# EtherCAT_Sheet.net
KiCad netlist of a schematic drawn in Altium Designer
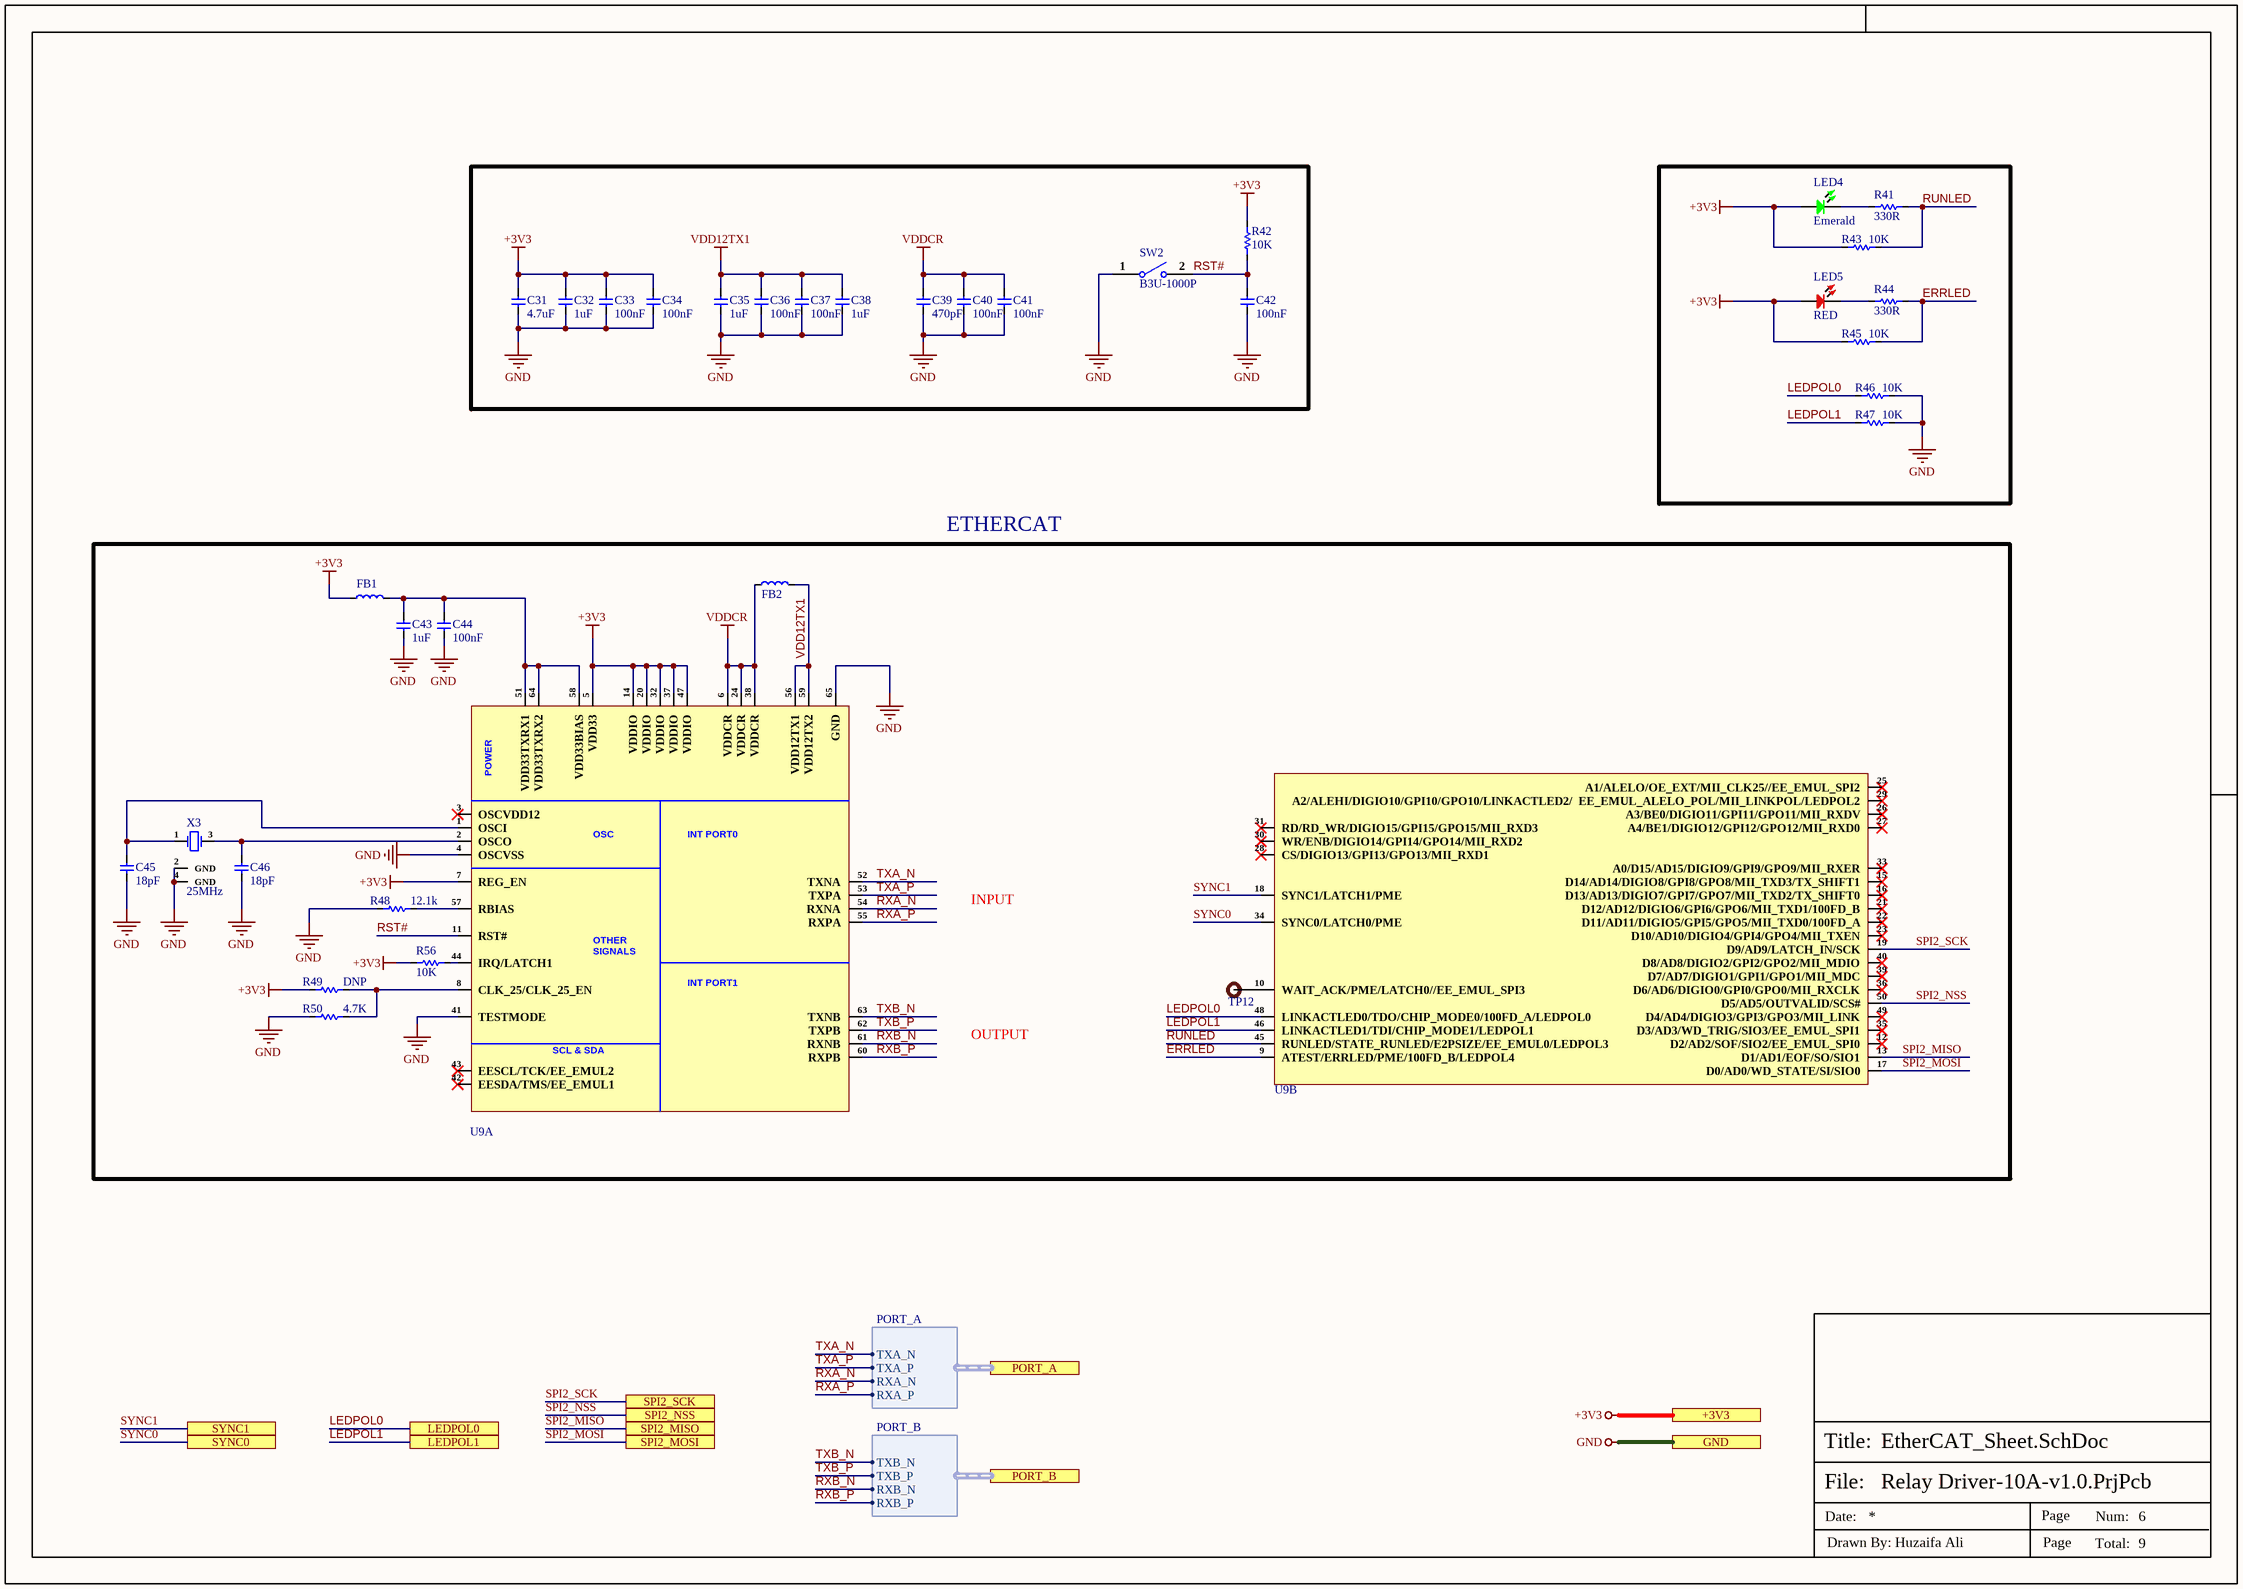
[diagram p0: EtherCAT_Sheet.SchDoc]

(export (version "E")
  (design (tool "Eeschema 10.0.6"))
  (components
    (comp (ref "C31")
      (value "4.7uF")
      (footprint "Cap-0402")
      (description "CAP CER 4.7UF 10V X5R 0402")
      (fields
        (field (name "MANUFACTURER") "Yageo")
        (field (name "MANUFACTURER PART NUMBER") "CC0402KRX5R6BB475")
      )
      (libsource (lib "eSpark Libraries") (part "CC0402KRX5R6BB475"))
    )
    (comp (ref "C32")
      (value "1uF")
      (footprint "Cap-0402")
      (description "CAP CER 1UF 10V X5R 0402")
      (fields
        (field (name "MANUFACTURER") "Yageo")
        (field (name "MANUFACTURER PART NUMBER") "CC0402KRX5R6BB105")
      )
      (libsource (lib "eSpark Libraries") (part "CC0402KRX5R6BB105"))
    )
    (comp (ref "C33")
      (value "100nF")
      (footprint "cap-0402")
      (description "CAP CER 0.1UF 50V X7R 0402")
      (fields
        (field (name "MANUFACTURER") "TDK")
        (field (name "MANUFACTURER PART NUMBER") "C1005X7R1H104KT000F")
      )
      (libsource (lib "eSpark Libraries") (part "C1005X7R1H104KT000F"))
    )
    (comp (ref "C34")
      (value "100nF")
      (footprint "cap-0402")
      (description "CAP CER 0.1UF 50V X7R 0402")
      (fields
        (field (name "MANUFACTURER") "TDK")
        (field (name "MANUFACTURER PART NUMBER") "C1005X7R1H104KT000F")
      )
      (libsource (lib "eSpark Libraries") (part "C1005X7R1H104KT000F"))
    )
    (comp (ref "C35")
      (value "1uF")
      (footprint "Cap-0402")
      (description "CAP CER 1UF 10V X5R 0402")
      (fields
        (field (name "MANUFACTURER") "Yageo")
        (field (name "MANUFACTURER PART NUMBER") "CC0402KRX5R6BB105")
      )
      (libsource (lib "eSpark Libraries") (part "CC0402KRX5R6BB105"))
    )
    (comp (ref "C36")
      (value "100nF")
      (footprint "cap-0402")
      (description "CAP CER 0.1UF 50V X7R 0402")
      (fields
        (field (name "MANUFACTURER") "TDK")
        (field (name "MANUFACTURER PART NUMBER") "C1005X7R1H104KT000F")
      )
      (libsource (lib "eSpark Libraries") (part "C1005X7R1H104KT000F"))
    )
    (comp (ref "C37")
      (value "100nF")
      (footprint "cap-0402")
      (description "CAP CER 0.1UF 50V X7R 0402")
      (fields
        (field (name "MANUFACTURER") "TDK")
        (field (name "MANUFACTURER PART NUMBER") "C1005X7R1H104KT000F")
      )
      (libsource (lib "eSpark Libraries") (part "C1005X7R1H104KT000F"))
    )
    (comp (ref "C38")
      (value "1uF")
      (footprint "Cap-0402")
      (description "CAP CER 1UF 10V X5R 0402")
      (fields
        (field (name "MANUFACTURER") "Yageo")
        (field (name "MANUFACTURER PART NUMBER") "CC0402KRX5R6BB105")
      )
      (libsource (lib "eSpark Libraries") (part "CC0402KRX5R6BB105"))
    )
    (comp (ref "C39")
      (value "470pF")
      (footprint "Cap-0603")
      (description "CAP CER 470PF 50V X7R 0603")
      (fields
        (field (name "MANUFACTURER") "Walsin Technologies")
        (field (name "MANUFACTURER PART NUMBER") "0603B471K500CT")
      )
      (libsource (lib "eSpark Libraries") (part "0603B471K500CT"))
    )
    (comp (ref "C40")
      (value "100nF")
      (footprint "cap-0402")
      (description "CAP CER 0.1UF 50V X7R 0402")
      (fields
        (field (name "MANUFACTURER") "TDK")
        (field (name "MANUFACTURER PART NUMBER") "C1005X7R1H104KT000F")
      )
      (libsource (lib "eSpark Libraries") (part "C1005X7R1H104KT000F"))
    )
    (comp (ref "C41")
      (value "100nF")
      (footprint "cap-0402")
      (description "CAP CER 0.1UF 50V X7R 0402")
      (fields
        (field (name "MANUFACTURER") "TDK")
        (field (name "MANUFACTURER PART NUMBER") "C1005X7R1H104KT000F")
      )
      (libsource (lib "eSpark Libraries") (part "C1005X7R1H104KT000F"))
    )
    (comp (ref "C42")
      (value "100nF")
      (footprint "cap-0402")
      (description "CAP CER 0.1UF 50V X7R 0402")
      (fields
        (field (name "MANUFACTURER") "TDK")
        (field (name "MANUFACTURER PART NUMBER") "C1005X7R1H104KT000F")
      )
      (libsource (lib "eSpark Libraries") (part "C1005X7R1H104KT000F"))
    )
    (comp (ref "C43")
      (value "1uF")
      (footprint "Cap-0402")
      (description "CAP CER 1UF 10V X5R 0402")
      (fields
        (field (name "MANUFACTURER") "Yageo")
        (field (name "MANUFACTURER PART NUMBER") "CC0402KRX5R6BB105")
      )
      (libsource (lib "eSpark Libraries") (part "CC0402KRX5R6BB105"))
    )
    (comp (ref "C44")
      (value "100nF")
      (footprint "cap-0402")
      (description "CAP CER 0.1UF 50V X7R 0402")
      (fields
        (field (name "MANUFACTURER") "TDK")
        (field (name "MANUFACTURER PART NUMBER") "C1005X7R1H104KT000F")
      )
      (libsource (lib "eSpark Libraries") (part "C1005X7R1H104KT000F"))
    )
    (comp (ref "C45")
      (value "18pF")
      (footprint "Cap-0402")
      (description "CAP CER 18PF 50V C0G/NP0 0402")
      (fields
        (field (name "MANUFACTURER") "Murata")
        (field (name "MANUFACTURER PART NUMBER") "GCM1555C1H180GA16D")
      )
      (libsource (lib "eSpark Libraries") (part "GCM1555C1H180GA16D"))
    )
    (comp (ref "C46")
      (value "18pF")
      (footprint "Cap-0402")
      (description "CAP CER 18PF 50V C0G/NP0 0402")
      (fields
        (field (name "MANUFACTURER") "Murata")
        (field (name "MANUFACTURER PART NUMBER") "GCM1555C1H180GA16D")
      )
      (libsource (lib "eSpark Libraries") (part "GCM1555C1H180GA16D"))
    )
    (comp (ref "FB1")
      (value "BLM15PG100SN1D")
      (footprint "IND-0402")
      (description "FERRITE BEAD 10 OHM 0402 1LN")
      (fields (field (name "MANUFACTURER") "Murata") (field (name "TOLERANCE") "25%"))
      (libsource (lib "eSpark Libraries") (part "BLM15PG100SN1D"))
    )
    (comp (ref "FB2")
      (value "BLM15PG100SN1D")
      (footprint "IND-0402")
      (description "FERRITE BEAD 10 OHM 0402 1LN")
      (fields (field (name "MANUFACTURER") "Murata") (field (name "TOLERANCE") "25%"))
      (libsource (lib "eSpark Libraries") (part "BLM15PG100SN1D"))
    )
    (comp (ref "LED4")
      (value "Emerald")
      (footprint "LED-0603")
      (description "Emerald 0603 Light Emitting Diodes (LED) ROHS")
      (fields
        (field (name "MANUFACTURER") "Foshan NationStar Optoelectronics")
        (field (name "MANUFACTURER PART NUMBER") "NCD0603G2")
      )
      (libsource (lib "eSpark Libraries") (part "NCD0603G2"))
    )
    (comp (ref "LED5")
      (value "RED")
      (footprint "LED-0603")
      (description "RED LED 0603 Light Emitting Diodes")
      (fields
        (field (name "MANUFACTURER") "Foshan NationStar Optoelectronics")
        (field (name "MANUFACTURER PART NUMBER") "NCD0603R3")
      )
      (libsource (lib "eSpark Libraries") (part "NCD0603R3"))
    )
    (comp (ref "R41")
      (value "330R")
      (footprint "Res-0603")
      (description "RES  SMD 330R 100 mW 0603")
      (fields
        (field (name "MANUFACTURER") "Yageo")
        (field (name "MANUFACTURER PART NUMBER") "RC0603JR-07330RL")
      )
      (libsource (lib "eSpark Libraries") (part "RC0603JR-07330RL"))
    )
    (comp (ref "R42")
      (value "10K")
      (footprint "Res-0402")
      (description "RES 10K OHM 1% 1/16W 0402")
      (fields
        (field (name "MANUFACTURER") "Yageo")
        (field (name "MANUFACTURER PART NUMBER") "RC0402FR-0710KL")
      )
      (libsource (lib "eSpark Libraries") (part "RC0402FR-0710KL"))
    )
    (comp (ref "R43")
      (value "10K")
      (footprint "Res-0402")
      (description "RES 10K OHM 1% 1/16W 0402")
      (fields
        (field (name "MANUFACTURER") "Yageo")
        (field (name "MANUFACTURER PART NUMBER") "RC0402FR-0710KL")
      )
      (libsource (lib "eSpark Libraries") (part "RC0402FR-0710KL"))
    )
    (comp (ref "R44")
      (value "330R")
      (footprint "Res-0603")
      (description "RES  SMD 330R 100 mW 0603")
      (fields
        (field (name "MANUFACTURER") "Yageo")
        (field (name "MANUFACTURER PART NUMBER") "RC0603JR-07330RL")
      )
      (libsource (lib "eSpark Libraries") (part "RC0603JR-07330RL"))
    )
    (comp (ref "R45")
      (value "10K")
      (footprint "Res-0402")
      (description "RES 10K OHM 1% 1/16W 0402")
      (fields
        (field (name "MANUFACTURER") "Yageo")
        (field (name "MANUFACTURER PART NUMBER") "RC0402FR-0710KL")
      )
      (libsource (lib "eSpark Libraries") (part "RC0402FR-0710KL"))
    )
    (comp (ref "R46")
      (value "10K")
      (footprint "Res-0402")
      (description "RES 10K OHM 1% 1/16W 0402")
      (fields
        (field (name "MANUFACTURER") "Yageo")
        (field (name "MANUFACTURER PART NUMBER") "RC0402FR-0710KL")
      )
      (libsource (lib "eSpark Libraries") (part "RC0402FR-0710KL"))
    )
    (comp (ref "R47")
      (value "10K")
      (footprint "Res-0402")
      (description "RES 10K OHM 1% 1/16W 0402")
      (fields
        (field (name "MANUFACTURER") "Yageo")
        (field (name "MANUFACTURER PART NUMBER") "RC0402FR-0710KL")
      )
      (libsource (lib "eSpark Libraries") (part "RC0402FR-0710KL"))
    )
    (comp (ref "R48")
      (value "12.1k")
      (footprint "Res-0402")
      (description "RES SMD 12.1KOHM 0.1% 1/16W 0402")
      (fields
        (field (name "MANUFACTURER") "Yageo")
        (field (name "MANUFACTURER PART NUMBER") "RT0402BRD0712K1L")
      )
      (libsource (lib "eSpark Libraries") (part "RT0402BRD0712K1L"))
    )
    (comp (ref "R49")
      (value "DNP")
      (footprint "Res-0402")
      (description "RES 4.7K OHM 1% 1/16W 0402")
      (fields
        (field (name "MANUFACTURER") "Yageo")
        (field (name "MANUFACTURER PART NUMBER") "RC0402FR-074K7L")
      )
      (libsource (lib "eSpark Libraries") (part "RC0402FR-074K7L"))
    )
    (comp (ref "R50")
      (value "4.7K")
      (footprint "Res-0402")
      (description "RES 4.7K OHM 1% 1/16W 0402")
      (fields
        (field (name "MANUFACTURER") "Yageo")
        (field (name "MANUFACTURER PART NUMBER") "RC0402FR-074K7L")
      )
      (libsource (lib "eSpark Libraries") (part "RC0402FR-074K7L"))
    )
    (comp (ref "R56")
      (value "10K")
      (footprint "Res-0402")
      (description "RES 10K OHM 1% 1/16W 0402")
      (fields
        (field (name "MANUFACTURER") "Yageo")
        (field (name "MANUFACTURER PART NUMBER") "RC0402FR-0710KL")
      )
      (libsource (lib "eSpark Libraries") (part "RC0402FR-0710KL"))
    )
    (comp (ref "SW2")
      (value "B3U-1000P")
      (footprint "B3U-1000P")
      (description "SWITCH TACTILE SPST-NO 0.05A 12V")
      (fields (field (name "MANUFACTURER") "Omron") (field (name "LCSC PART NUMBER") "C231329"))
      (libsource (lib "eSpark Libraries") (part "B3U-1000P"))
    )
    (comp (ref "TP12")
      (value "TEST POINT")
      (footprint "Test-point")
      (description "Test Point ON")
      (libsource (lib "eSpark Libraries") (part "TEST POINT"))
    )
    (comp (ref "U9")
      (value "LAN9253-SVB QFN64")
      (footprint "QFN-64-EP(9x9)")
      (description "2/3-PORT ETHERCAT SLAVE CTLR")
      (fields
        (field (name "MANUFACTURER") "Microchip")
        (field (name "MANUFACTURER PART NUMBER") "LAN9253-I/R4X")
      )
      (libsource (lib "eSpark Libraries") (part "LAN9253-SVB QFN64"))
    )
    (comp (ref "X3")
      (value "25MHz")
      (footprint "SMD3225-4P")
      (description "25MHz 贴片晶振 18pF ±10ppm ±20ppm SMD3225-4P Crystals ROHS")
      (fields (field (name "LCSC PART NUMBER") "C70593") (field (name "MANUFACTURER") "YXC"))
      (libsource (lib "eSpark Libraries") (part "X322525MRB4SI"))
    )
  )
  (nets
    (net (code "3") (name "+3V3") (class "Default")
      (node (ref "C31") (pin "2") (pinfunction "2_2") (pintype "passive"))
      (node (ref "C32") (pin "2") (pinfunction "2_2") (pintype "passive"))
      (node (ref "C33") (pin "2") (pinfunction "2_2") (pintype "passive"))
      (node (ref "C34") (pin "2") (pinfunction "2_2") (pintype "passive"))
      (node (ref "FB1") (pin "1") (pinfunction "1_1") (pintype "passive"))
      (node (ref "LED4") (pin "1") (pinfunction "1_1") (pintype "passive"))
      (node (ref "LED5") (pin "1") (pinfunction "1_1") (pintype "passive"))
      (node (ref "R42") (pin "1") (pinfunction "1_1") (pintype "passive"))
      (node (ref "R43") (pin "2") (pinfunction "2_2") (pintype "passive"))
      (node (ref "R45") (pin "2") (pinfunction "2_2") (pintype "passive"))
      (node (ref "R49") (pin "1") (pinfunction "1_1") (pintype "passive"))
      (node (ref "R56") (pin "1") (pinfunction "1_1") (pintype "passive"))
      (node (ref "U9") (pin "14") (pinfunction "VDDIO_14") (pintype "passive"))
      (node (ref "U9") (pin "20") (pinfunction "VDDIO_20") (pintype "passive"))
      (node (ref "U9") (pin "32") (pinfunction "VDDIO_32") (pintype "passive"))
      (node (ref "U9") (pin "37") (pinfunction "VDDIO_37") (pintype "passive"))
      (node (ref "U9") (pin "47") (pinfunction "VDDIO_47") (pintype "passive"))
      (node (ref "U9") (pin "5") (pinfunction "VDD33_5") (pintype "passive"))
      (node (ref "U9") (pin "7") (pinfunction "REG_EN_7") (pintype "passive"))
    )
    (net (code "4") (name "/ERRLED") (class "Default")
      (node (ref "R44") (pin "2") (pinfunction "2_2") (pintype "passive"))
      (node (ref "R45") (pin "1") (pinfunction "1_1") (pintype "passive"))
      (node (ref "U9") (pin "9") (pinfunction "ATEST/ERRLED/PME/100FD_B/LEDPOL4_9") (pintype "passive"))
    )
    (net (code "5") (name "/LEDPOL0") (class "Default")
      (node (ref "R46") (pin "2") (pinfunction "2_2") (pintype "passive"))
      (node (ref "U9") (pin "48") (pinfunction "LINKACTLED0/TDO/CHIP_MODE0/100FD_A/LEDPOL0_48") (pintype "passive"))
    )
    (net (code "6") (name "/LEDPOL1") (class "Default")
      (node (ref "R47") (pin "2") (pinfunction "2_2") (pintype "passive"))
      (node (ref "U9") (pin "46") (pinfunction "LINKACTLED1/TDI/CHIP_MODE1/LEDPOL1_46") (pintype "passive"))
    )
    (net (code "7") (name "/RST#") (class "Default")
      (node (ref "C42") (pin "2") (pinfunction "2_2") (pintype "passive"))
      (node (ref "R42") (pin "2") (pinfunction "2_2") (pintype "passive"))
      (node (ref "SW2") (pin "2") (pinfunction "2_2") (pintype "passive"))
      (node (ref "U9") (pin "11") (pinfunction "RST#_11") (pintype "passive"))
    )
    (net (code "8") (name "/RUNLED") (class "Default")
      (node (ref "R41") (pin "2") (pinfunction "2_2") (pintype "passive"))
      (node (ref "R43") (pin "1") (pinfunction "1_1") (pintype "passive"))
      (node (ref "U9") (pin "45") (pinfunction "RUNLED/STATE_RUNLED/E2PSIZE/EE_EMUL0/LEDPOL3_45") (pintype "passive"))
    )
    (net (code "9") (name "/RXA_N") (class "Default")
      (node (ref "U9") (pin "54") (pinfunction "RXNA_54") (pintype "passive"))
    )
    (net (code "10") (name "/RXA_P") (class "Default")
      (node (ref "U9") (pin "55") (pinfunction "RXPA_55") (pintype "passive"))
    )
    (net (code "11") (name "/RXB_N") (class "Default")
      (node (ref "U9") (pin "61") (pinfunction "RXNB_61") (pintype "passive"))
    )
    (net (code "12") (name "/RXB_P") (class "Default")
      (node (ref "U9") (pin "60") (pinfunction "RXPB_60") (pintype "passive"))
    )
    (net (code "13") (name "/SPI2_MISO") (class "Default")
      (node (ref "U9") (pin "13") (pinfunction "D1/AD1/EOF/SO/SIO1_13") (pintype "passive"))
    )
    (net (code "14") (name "/SPI2_MOSI") (class "Default")
      (node (ref "U9") (pin "17") (pinfunction "D0/AD0/WD_STATE/SI/SIO0_17") (pintype "passive"))
    )
    (net (code "15") (name "/SPI2_NSS") (class "Default")
      (node (ref "U9") (pin "50") (pinfunction "D5/AD5/OUTVALID/SCS#_50") (pintype "passive"))
    )
    (net (code "16") (name "/SPI2_SCK") (class "Default")
      (node (ref "U9") (pin "19") (pinfunction "D9/AD9/LATCH_IN/SCK_19") (pintype "passive"))
    )
    (net (code "17") (name "/SYNC0") (class "Default")
      (node (ref "U9") (pin "34") (pinfunction "SYNC0/LATCH0/PME_34") (pintype "passive"))
    )
    (net (code "18") (name "/SYNC1") (class "Default")
      (node (ref "U9") (pin "18") (pinfunction "SYNC1/LATCH1/PME_18") (pintype "passive"))
    )
    (net (code "19") (name "/TXA_N") (class "Default")
      (node (ref "U9") (pin "52") (pinfunction "TXNA_52") (pintype "passive"))
    )
    (net (code "20") (name "/TXA_P") (class "Default")
      (node (ref "U9") (pin "53") (pinfunction "TXPA_53") (pintype "passive"))
    )
    (net (code "21") (name "/TXB_N") (class "Default")
      (node (ref "U9") (pin "63") (pinfunction "TXNB_63") (pintype "passive"))
    )
    (net (code "22") (name "/TXB_P") (class "Default")
      (node (ref "U9") (pin "62") (pinfunction "TXPB_62") (pintype "passive"))
    )
    (net (code "25") (name "GND") (class "Default")
      (node (ref "C31") (pin "1") (pinfunction "1_1") (pintype "passive"))
      (node (ref "C32") (pin "1") (pinfunction "1_1") (pintype "passive"))
      (node (ref "C33") (pin "1") (pinfunction "1_1") (pintype "passive"))
      (node (ref "C34") (pin "1") (pinfunction "1_1") (pintype "passive"))
      (node (ref "C35") (pin "1") (pinfunction "1_1") (pintype "passive"))
      (node (ref "C36") (pin "1") (pinfunction "1_1") (pintype "passive"))
      (node (ref "C37") (pin "1") (pinfunction "1_1") (pintype "passive"))
      (node (ref "C38") (pin "1") (pinfunction "1_1") (pintype "passive"))
      (node (ref "C39") (pin "1") (pinfunction "1_1") (pintype "passive"))
      (node (ref "C40") (pin "1") (pinfunction "1_1") (pintype "passive"))
      (node (ref "C41") (pin "1") (pinfunction "1_1") (pintype "passive"))
      (node (ref "C42") (pin "1") (pinfunction "1_1") (pintype "passive"))
      (node (ref "C43") (pin "1") (pinfunction "1_1") (pintype "passive"))
      (node (ref "C44") (pin "1") (pinfunction "1_1") (pintype "passive"))
      (node (ref "C45") (pin "2") (pinfunction "2_2") (pintype "passive"))
      (node (ref "C46") (pin "2") (pinfunction "2_2") (pintype "passive"))
      (node (ref "R46") (pin "1") (pinfunction "1_1") (pintype "passive"))
      (node (ref "R47") (pin "1") (pinfunction "1_1") (pintype "passive"))
      (node (ref "R48") (pin "1") (pinfunction "1_1") (pintype "passive"))
      (node (ref "R50") (pin "1") (pinfunction "1_1") (pintype "passive"))
      (node (ref "SW2") (pin "1") (pinfunction "1_1") (pintype "passive"))
      (node (ref "U9") (pin "4") (pinfunction "OSCVSS_4") (pintype "passive"))
      (node (ref "U9") (pin "41") (pinfunction "TESTMODE_41") (pintype "passive"))
      (node (ref "U9") (pin "65") (pinfunction "GND_65") (pintype "passive"))
      (node (ref "X3") (pin "2") (pinfunction "GND_2") (pintype "passive"))
      (node (ref "X3") (pin "4") (pinfunction "GND_4") (pintype "passive"))
    )
    (net (code "26") (name "Net-(LED4-Pad2)") (class "Default")
      (node (ref "LED4") (pin "2") (pinfunction "2_2") (pintype "passive"))
      (node (ref "R41") (pin "1") (pinfunction "1_1") (pintype "passive"))
    )
    (net (code "27") (name "Net-(LED5-Pad2)") (class "Default")
      (node (ref "LED5") (pin "2") (pinfunction "2_2") (pintype "passive"))
      (node (ref "R44") (pin "1") (pinfunction "1_1") (pintype "passive"))
    )
    (net (code "28") (name "Net-(U9A-CLK_25{slash}CLK_25_EN)") (class "Default")
      (node (ref "R49") (pin "2") (pinfunction "2_2") (pintype "passive"))
      (node (ref "R50") (pin "2") (pinfunction "2_2") (pintype "passive"))
      (node (ref "U9") (pin "8") (pinfunction "CLK_25/CLK_25_EN_8") (pintype "passive"))
    )
    (net (code "29") (name "Net-(U9A-IRQ{slash}LATCH1)") (class "Default")
      (node (ref "R56") (pin "2") (pinfunction "2_2") (pintype "passive"))
      (node (ref "U9") (pin "44") (pinfunction "IRQ/LATCH1_44") (pintype "passive"))
    )
    (net (code "30") (name "Net-(U9A-OSCI)") (class "Default")
      (node (ref "C45") (pin "1") (pinfunction "1_1") (pintype "passive"))
      (node (ref "U9") (pin "1") (pinfunction "OSCI_1") (pintype "passive"))
      (node (ref "X3") (pin "1") (pinfunction "CRYSTAL_1") (pintype "passive"))
    )
    (net (code "31") (name "Net-(U9A-OSCO)") (class "Default")
      (node (ref "C46") (pin "1") (pinfunction "1_1") (pintype "passive"))
      (node (ref "U9") (pin "2") (pinfunction "OSCO_2") (pintype "passive"))
      (node (ref "X3") (pin "3") (pinfunction "CRYSTAL_3") (pintype "passive"))
    )
    (net (code "32") (name "Net-(U9A-RBIAS)") (class "Default")
      (node (ref "R48") (pin "2") (pinfunction "2_2") (pintype "passive"))
      (node (ref "U9") (pin "57") (pinfunction "RBIAS_57") (pintype "passive"))
    )
    (net (code "33") (name "Net-(U9A-VDD33BIAS)") (class "Default")
      (node (ref "C43") (pin "2") (pinfunction "2_2") (pintype "passive"))
      (node (ref "C44") (pin "2") (pinfunction "2_2") (pintype "passive"))
      (node (ref "FB1") (pin "2") (pinfunction "2_2") (pintype "passive"))
      (node (ref "U9") (pin "51") (pinfunction "VDD33TXRX1_51") (pintype "passive"))
      (node (ref "U9") (pin "58") (pinfunction "VDD33BIAS_58") (pintype "passive"))
      (node (ref "U9") (pin "64") (pinfunction "VDD33TXRX2_64") (pintype "passive"))
    )
    (net (code "34") (name "Net-(U9B-WAIT_ACK{slash}PME{slash}LATCH0{slash}{slash}EE_EMUL_SPI3)") (class "Default")
      (node (ref "TP12") (pin "1") (pinfunction "1_1") (pintype "passive"))
      (node (ref "U9") (pin "10") (pinfunction "WAIT_ACK/PME/LATCH0//EE_EMUL_SPI3_10") (pintype "passive"))
    )
    (net (code "35") (name "VDD12TX1") (class "Default")
      (node (ref "C35") (pin "2") (pinfunction "2_2") (pintype "passive"))
      (node (ref "C36") (pin "2") (pinfunction "2_2") (pintype "passive"))
      (node (ref "C37") (pin "2") (pinfunction "2_2") (pintype "passive"))
      (node (ref "C38") (pin "2") (pinfunction "2_2") (pintype "passive"))
      (node (ref "FB2") (pin "2") (pinfunction "2_2") (pintype "passive"))
      (node (ref "U9") (pin "56") (pinfunction "VDD12TX1_56") (pintype "passive"))
      (node (ref "U9") (pin "59") (pinfunction "VDD12TX2_59") (pintype "passive"))
    )
    (net (code "36") (name "VDDCR") (class "Default")
      (node (ref "C39") (pin "2") (pinfunction "2_2") (pintype "passive"))
      (node (ref "C40") (pin "2") (pinfunction "2_2") (pintype "passive"))
      (node (ref "C41") (pin "2") (pinfunction "2_2") (pintype "passive"))
      (node (ref "FB2") (pin "1") (pinfunction "1_1") (pintype "passive"))
      (node (ref "U9") (pin "24") (pinfunction "VDDCR_24") (pintype "passive"))
      (node (ref "U9") (pin "38") (pinfunction "VDDCR_38") (pintype "passive"))
      (node (ref "U9") (pin "6") (pinfunction "VDDCR_6") (pintype "passive"))
    )
    (net (code "37") (name "unconnected-(U9A-EESCL{slash}TCK{slash}EE_EMUL2-Pad43)") (class "Default")
      (node (ref "U9") (pin "43") (pinfunction "EESCL/TCK/EE_EMUL2_43") (pintype "passive+no_connect"))
    )
    (net (code "38") (name "unconnected-(U9A-EESDA{slash}TMS{slash}EE_EMUL1-Pad42)") (class "Default")
      (node (ref "U9") (pin "42") (pinfunction "EESDA/TMS/EE_EMUL1_42") (pintype "passive+no_connect"))
    )
    (net (code "39") (name "unconnected-(U9A-OSCVDD12-Pad3)") (class "Default")
      (node (ref "U9") (pin "3") (pinfunction "OSCVDD12_3") (pintype "passive+no_connect"))
    )
    (net (code "40") (name "unconnected-(U9B-A0{slash}D15{slash}AD15{slash}DIGIO9{slash}GPI9{slash}GPO9{slash}MII_RXER-Pad33)") (class "Default")
      (node (ref "U9") (pin "33") (pinfunction "A0/D15/AD15/DIGIO9/GPI9/GPO9/MII_RXER_33") (pintype "passive+no_connect"))
    )
    (net (code "41") (name "unconnected-(U9B-A1{slash}ALELO{slash}OE_EXT{slash}MII_CLK25{slash}{slash}EE_EMUL_SPI2-Pad25)") (class "Default")
      (node (ref "U9") (pin "25") (pinfunction "A1/ALELO/OE_EXT/MII_CLK25//EE_EMUL_SPI2_25") (pintype "passive+no_connect"))
    )
    (net (code "42") (name "unconnected-(U9B-A2{slash}ALEHI{slash}DIGIO10{slash}GPI10{slash}GPO10{slash}LINKACTLED2{slash}__EE_EMUL_ALELO_POL{slash}MII_LINKPOL{slash}LEDPOL2-Pad29)") (class "Default")
      (node (ref "U9") (pin "29") (pinfunction "A2/ALEHI/DIGIO10/GPI10/GPO10/LINKACTLED2/__EE_EMUL_ALELO_POL/MII_LINKPOL/LEDPOL2_29") (pintype "passive+no_connect"))
    )
    (net (code "43") (name "unconnected-(U9B-A3{slash}BE0{slash}DIGIO11{slash}GPI11{slash}GPO11{slash}MII_RXDV-Pad26)") (class "Default")
      (node (ref "U9") (pin "26") (pinfunction "A3/BE0/DIGIO11/GPI11/GPO11/MII_RXDV_26") (pintype "passive+no_connect"))
    )
    (net (code "44") (name "unconnected-(U9B-A4{slash}BE1{slash}DIGIO12{slash}GPI12{slash}GPO12{slash}MII_RXD0-Pad27)") (class "Default")
      (node (ref "U9") (pin "27") (pinfunction "A4/BE1/DIGIO12/GPI12/GPO12/MII_RXD0_27") (pintype "passive+no_connect"))
    )
    (net (code "45") (name "unconnected-(U9B-CS{slash}DIGIO13{slash}GPI13{slash}GPO13{slash}MII_RXD1-Pad28)") (class "Default")
      (node (ref "U9") (pin "28") (pinfunction "CS/DIGIO13/GPI13/GPO13/MII_RXD1_28") (pintype "passive+no_connect"))
    )
    (net (code "46") (name "unconnected-(U9B-D2{slash}AD2{slash}SOF{slash}SIO2{slash}EE_EMUL_SPI0-Pad12)") (class "Default")
      (node (ref "U9") (pin "12") (pinfunction "D2/AD2/SOF/SIO2/EE_EMUL_SPI0_12") (pintype "passive+no_connect"))
    )
    (net (code "47") (name "unconnected-(U9B-D3{slash}AD3{slash}WD_TRIG{slash}SIO3{slash}EE_EMUL_SPI1-Pad35)") (class "Default")
      (node (ref "U9") (pin "35") (pinfunction "D3/AD3/WD_TRIG/SIO3/EE_EMUL_SPI1_35") (pintype "passive+no_connect"))
    )
    (net (code "48") (name "unconnected-(U9B-D4{slash}AD4{slash}DIGIO3{slash}GPI3{slash}GPO3{slash}MII_LINK-Pad49)") (class "Default")
      (node (ref "U9") (pin "49") (pinfunction "D4/AD4/DIGIO3/GPI3/GPO3/MII_LINK_49") (pintype "passive+no_connect"))
    )
    (net (code "49") (name "unconnected-(U9B-D6{slash}AD6{slash}DIGIO0{slash}GPI0{slash}GPO0{slash}MII_RXCLK-Pad36)") (class "Default")
      (node (ref "U9") (pin "36") (pinfunction "D6/AD6/DIGIO0/GPI0/GPO0/MII_RXCLK_36") (pintype "passive+no_connect"))
    )
    (net (code "50") (name "unconnected-(U9B-D7{slash}AD7{slash}DIGIO1{slash}GPI1{slash}GPO1{slash}MII_MDC-Pad39)") (class "Default")
      (node (ref "U9") (pin "39") (pinfunction "D7/AD7/DIGIO1/GPI1/GPO1/MII_MDC_39") (pintype "passive+no_connect"))
    )
    (net (code "51") (name "unconnected-(U9B-D8{slash}AD8{slash}DIGIO2{slash}GPI2{slash}GPO2{slash}MII_MDIO-Pad40)") (class "Default")
      (node (ref "U9") (pin "40") (pinfunction "D8/AD8/DIGIO2/GPI2/GPO2/MII_MDIO_40") (pintype "passive+no_connect"))
    )
    (net (code "52") (name "unconnected-(U9B-D10{slash}AD10{slash}DIGIO4{slash}GPI4{slash}GPO4{slash}MII_TXEN-Pad23)") (class "Default")
      (node (ref "U9") (pin "23") (pinfunction "D10/AD10/DIGIO4/GPI4/GPO4/MII_TXEN_23") (pintype "passive+no_connect"))
    )
    (net (code "53") (name "unconnected-(U9B-D11{slash}AD11{slash}DIGIO5{slash}GPI5{slash}GPO5{slash}MII_TXD0{slash}100FD_A-Pad22)") (class "Default")
      (node (ref "U9") (pin "22") (pinfunction "D11/AD11/DIGIO5/GPI5/GPO5/MII_TXD0/100FD_A_22") (pintype "passive+no_connect"))
    )
    (net (code "54") (name "unconnected-(U9B-D12{slash}AD12{slash}DIGIO6{slash}GPI6{slash}GPO6{slash}MII_TXD1{slash}100FD_B-Pad21)") (class "Default")
      (node (ref "U9") (pin "21") (pinfunction "D12/AD12/DIGIO6/GPI6/GPO6/MII_TXD1/100FD_B_21") (pintype "passive+no_connect"))
    )
    (net (code "55") (name "unconnected-(U9B-D13{slash}AD13{slash}DIGIO7{slash}GPI7{slash}GPO7{slash}MII_TXD2{slash}TX_SHIFT0-Pad16)") (class "Default")
      (node (ref "U9") (pin "16") (pinfunction "D13/AD13/DIGIO7/GPI7/GPO7/MII_TXD2/TX_SHIFT0_16") (pintype "passive+no_connect"))
    )
    (net (code "56") (name "unconnected-(U9B-D14{slash}AD14{slash}DIGIO8{slash}GPI8{slash}GPO8{slash}MII_TXD3{slash}TX_SHIFT1-Pad15)") (class "Default")
      (node (ref "U9") (pin "15") (pinfunction "D14/AD14/DIGIO8/GPI8/GPO8/MII_TXD3/TX_SHIFT1_15") (pintype "passive+no_connect"))
    )
    (net (code "57") (name "unconnected-(U9B-RD{slash}RD_WR{slash}DIGIO15{slash}GPI15{slash}GPO15{slash}MII_RXD3-Pad31)") (class "Default")
      (node (ref "U9") (pin "31") (pinfunction "RD/RD_WR/DIGIO15/GPI15/GPO15/MII_RXD3_31") (pintype "passive+no_connect"))
    )
    (net (code "58") (name "unconnected-(U9B-WR{slash}ENB{slash}DIGIO14{slash}GPI14{slash}GPO14{slash}MII_RXD2-Pad30)") (class "Default")
      (node (ref "U9") (pin "30") (pinfunction "WR/ENB/DIGIO14/GPI14/GPO14/MII_RXD2_30") (pintype "passive+no_connect"))
    )
  )
)
